# Bluetooth.net
KiCad netlist of a schematic drawn in Altium Designer
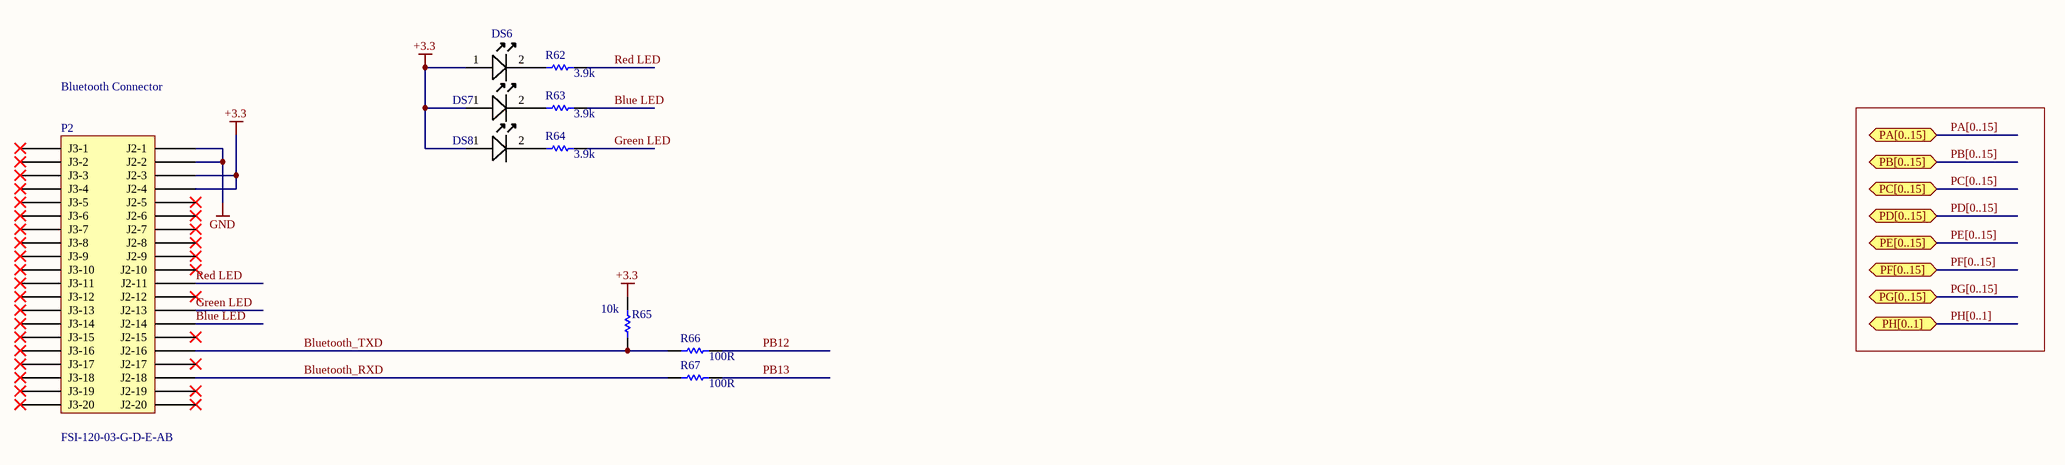
[diagram p0: Bluetooth.SchDoc]

(export (version "E")
  (design (tool "Eeschema 10.0.6"))
  (components
    (comp (ref "DS6")
      (value "Lite-On LTST-S220KGKT Green LED, 571 nm 2012 (0805) Side View, Rectangle Lens SMD package")
      (footprint "0805C_L")
      (fields
        (field (name "MANUFACTURER") "Vishay / Lite-On")
        (field (name "MANUFACTURER PART NUMBER") "LTST-S220KGKT")
      )
      (libsource (lib "*") (part "LED A/K"))
    )
    (comp (ref "DS7")
      (value "Lite-On LTST-S220KGKT Green LED, 571 nm 2012 (0805) Side View, Rectangle Lens SMD package")
      (footprint "0805C_L")
      (fields
        (field (name "MANUFACTURER") "Vishay / Lite-On")
        (field (name "MANUFACTURER PART NUMBER") "LTST-S220KGKT")
      )
      (libsource (lib "*") (part "LED A/K"))
    )
    (comp (ref "DS8")
      (value "Lite-On LTST-S220KGKT Green LED, 571 nm 2012 (0805) Side View, Rectangle Lens SMD package")
      (footprint "0805C_L")
      (fields
        (field (name "MANUFACTURER") "Vishay / Lite-On")
        (field (name "MANUFACTURER PART NUMBER") "LTST-S220KGKT")
      )
      (libsource (lib "*") (part "LED A/K"))
    )
    (comp (ref "P2")
      (value "FSI-120-03-G-D-E-AB")
      (footprint "FSI-120-03-G-D-E-AB")
      (fields
        (field (name "MANUFACTURER") "Samtec")
        (field (name "MANUFACTURER PART NUMBER") "FSI-120-03-G-D-E-AB")
      )
      (libsource (lib "ZLS_Schematic_lib") (part "FSI-120-03-G-D-E-AB"))
    )
    (comp (ref "R62")
      (value "CRCW08053K90FKEA")
      (footprint "RESC0805(2012)_M")
      (description "3.9 kOhms ±1% 0.125W, 1/8W Chip Resistor 0805 (2012 Metric) Automotive AEC-Q200 Thick Film")
      (fields
        (field (name "POWER") "0.125 W")
        (field (name "TOLERANCE") "1 %")
        (field (name "RESISTANCE") "3.9k")
      )
      (libsource (lib "Altium Content Vault") (part "RES"))
    )
    (comp (ref "R63")
      (value "CRCW08053K90FKEA")
      (footprint "RESC0805(2012)_M")
      (description "3.9 kOhms ±1% 0.125W, 1/8W Chip Resistor 0805 (2012 Metric) Automotive AEC-Q200 Thick Film")
      (fields
        (field (name "POWER") "0.125 W")
        (field (name "TOLERANCE") "1 %")
        (field (name "RESISTANCE") "3.9k")
      )
      (libsource (lib "Altium Content Vault") (part "RES"))
    )
    (comp (ref "R64")
      (value "CRCW08053K90FKEA")
      (footprint "RESC0805(2012)_M")
      (description "3.9 kOhms ±1% 0.125W, 1/8W Chip Resistor 0805 (2012 Metric) Automotive AEC-Q200 Thick Film")
      (fields
        (field (name "POWER") "0.125 W")
        (field (name "TOLERANCE") "1 %")
        (field (name "RESISTANCE") "3.9k")
      )
      (libsource (lib "Altium Content Vault") (part "RES"))
    )
    (comp (ref "R65")
      (value "CRCW080510K0FKEA")
      (footprint "RESC2013X50X30NL20T20")
      (description "10 kOhms ±1% 0.125W, 1/8W Chip Resistor 0805 (2012 Metric) Automotive AEC-Q200 Thick Film")
      (fields
        (field (name "MANUFACTURER") "Vishay Dale")
        (field (name "RESISTANCE") "10k")
        (field (name "TOLERANCE") "1%")
      )
      (libsource (lib "Altium Content Vault") (part "RES"))
    )
    (comp (ref "R66")
      (value "CRCW0805100RFKEA")
      (footprint "RESC2013X50X30LL20T20")
      (description "100 Ohms ±1% 0.125W, 1/8W Chip Resistor 0805 (2012 Metric) Thick Film")
      (fields
        (field (name "MANUFACTURER") "Vishay Dale")
        (field (name "RESISTANCE") "100R")
        (field (name "TOLERANCE") "1%")
      )
      (libsource (lib "Altium Content Vault") (part "RES"))
    )
    (comp (ref "R67")
      (value "CRCW0805100RFKEA")
      (footprint "RESC2013X50X30LL20T20")
      (description "100 Ohms ±1% 0.125W, 1/8W Chip Resistor 0805 (2012 Metric) Thick Film")
      (fields
        (field (name "MANUFACTURER") "Vishay Dale")
        (field (name "RESISTANCE") "100R")
        (field (name "TOLERANCE") "1%")
      )
      (libsource (lib "Altium Content Vault") (part "RES"))
    )
  )
  (nets
    (net (code "113") (name "+3.3") (class "Default")
      (node (ref "DS6") (pin "1") (pinfunction "A_1") (pintype "passive"))
      (node (ref "DS7") (pin "1") (pinfunction "A_1") (pintype "passive"))
      (node (ref "DS8") (pin "1") (pinfunction "A_1") (pintype "passive"))
      (node (ref "P2") (pin "J2-3") (pinfunction "J2-3_J2-3") (pintype "passive"))
      (node (ref "P2") (pin "J2-4") (pinfunction "J2-4_J2-4") (pintype "passive"))
      (node (ref "R65") (pin "2") (pinfunction "2_2") (pintype "passive"))
    )
    (net (code "114") (name "/Blue LED") (class "Default")
      (node (ref "P2") (pin "J2-14") (pinfunction "J2-14_J2-14") (pintype "passive"))
      (node (ref "R63") (pin "2") (pinfunction "2_2") (pintype "passive"))
    )
    (net (code "115") (name "/Bluetooth_RXD") (class "Default")
      (node (ref "P2") (pin "J2-18") (pinfunction "J2-18_J2-18") (pintype "passive"))
      (node (ref "R67") (pin "1") (pinfunction "1_1") (pintype "passive"))
    )
    (net (code "116") (name "/Bluetooth_TXD") (class "Default")
      (node (ref "P2") (pin "J2-16") (pinfunction "J2-16_J2-16") (pintype "passive"))
      (node (ref "R65") (pin "1") (pinfunction "1_1") (pintype "passive"))
      (node (ref "R66") (pin "1") (pinfunction "1_1") (pintype "passive"))
    )
    (net (code "117") (name "/Green LED") (class "Default")
      (node (ref "P2") (pin "J2-13") (pinfunction "J2-13_J2-13") (pintype "passive"))
      (node (ref "R64") (pin "2") (pinfunction "2_2") (pintype "passive"))
    )
    (net (code "119") (name "/PB12") (class "Default")
      (node (ref "R66") (pin "2") (pinfunction "2_2") (pintype "passive"))
    )
    (net (code "120") (name "/PB13") (class "Default")
      (node (ref "R67") (pin "2") (pinfunction "2_2") (pintype "passive"))
    )
    (net (code "128") (name "/Red LED") (class "Default")
      (node (ref "P2") (pin "J2-11") (pinfunction "J2-11_J2-11") (pintype "passive"))
      (node (ref "R62") (pin "2") (pinfunction "2_2") (pintype "passive"))
    )
    (net (code "129") (name "GND") (class "Default")
      (node (ref "P2") (pin "J2-1") (pinfunction "J2-1_J2-1") (pintype "passive"))
      (node (ref "P2") (pin "J2-2") (pinfunction "J2-2_J2-2") (pintype "passive"))
    )
    (net (code "130") (name "Net-(DS6-K)") (class "Default")
      (node (ref "DS6") (pin "2") (pinfunction "K_2") (pintype "passive"))
      (node (ref "R62") (pin "1") (pinfunction "1_1") (pintype "passive"))
    )
    (net (code "131") (name "Net-(DS7-K)") (class "Default")
      (node (ref "DS7") (pin "2") (pinfunction "K_2") (pintype "passive"))
      (node (ref "R63") (pin "1") (pinfunction "1_1") (pintype "passive"))
    )
    (net (code "132") (name "Net-(DS8-K)") (class "Default")
      (node (ref "DS8") (pin "2") (pinfunction "K_2") (pintype "passive"))
      (node (ref "R64") (pin "1") (pinfunction "1_1") (pintype "passive"))
    )
    (net (code "133") (name "unconnected-(P2-PadJ2-5)") (class "Default")
      (node (ref "P2") (pin "J2-5") (pinfunction "J2-5_J2-5") (pintype "passive+no_connect"))
    )
    (net (code "134") (name "unconnected-(P2-PadJ2-6)") (class "Default")
      (node (ref "P2") (pin "J2-6") (pinfunction "J2-6_J2-6") (pintype "passive+no_connect"))
    )
    (net (code "135") (name "unconnected-(P2-PadJ2-7)") (class "Default")
      (node (ref "P2") (pin "J2-7") (pinfunction "J2-7_J2-7") (pintype "passive+no_connect"))
    )
    (net (code "136") (name "unconnected-(P2-PadJ2-8)") (class "Default")
      (node (ref "P2") (pin "J2-8") (pinfunction "J2-8_J2-8") (pintype "passive+no_connect"))
    )
    (net (code "137") (name "unconnected-(P2-PadJ2-9)") (class "Default")
      (node (ref "P2") (pin "J2-9") (pinfunction "J2-9_J2-9") (pintype "passive+no_connect"))
    )
    (net (code "138") (name "unconnected-(P2-PadJ2-10)") (class "Default")
      (node (ref "P2") (pin "J2-10") (pinfunction "J2-10_J2-10") (pintype "passive+no_connect"))
    )
    (net (code "139") (name "unconnected-(P2-PadJ2-12)") (class "Default")
      (node (ref "P2") (pin "J2-12") (pinfunction "J2-12_J2-12") (pintype "passive+no_connect"))
    )
    (net (code "140") (name "unconnected-(P2-PadJ2-15)") (class "Default")
      (node (ref "P2") (pin "J2-15") (pinfunction "J2-15_J2-15") (pintype "passive+no_connect"))
    )
    (net (code "141") (name "unconnected-(P2-PadJ2-17)") (class "Default")
      (node (ref "P2") (pin "J2-17") (pinfunction "J2-17_J2-17") (pintype "passive+no_connect"))
    )
    (net (code "142") (name "unconnected-(P2-PadJ2-19)") (class "Default")
      (node (ref "P2") (pin "J2-19") (pinfunction "J2-19_J2-19") (pintype "passive+no_connect"))
    )
    (net (code "143") (name "unconnected-(P2-PadJ2-20)") (class "Default")
      (node (ref "P2") (pin "J2-20") (pinfunction "J2-20_J2-20") (pintype "passive+no_connect"))
    )
    (net (code "144") (name "unconnected-(P2-PadJ3-1)") (class "Default")
      (node (ref "P2") (pin "J3-1") (pinfunction "J3-1_J3-1") (pintype "passive+no_connect"))
    )
    (net (code "145") (name "unconnected-(P2-PadJ3-2)") (class "Default")
      (node (ref "P2") (pin "J3-2") (pinfunction "J3-2_J3-2") (pintype "passive+no_connect"))
    )
    (net (code "146") (name "unconnected-(P2-PadJ3-3)") (class "Default")
      (node (ref "P2") (pin "J3-3") (pinfunction "J3-3_J3-3") (pintype "passive+no_connect"))
    )
    (net (code "147") (name "unconnected-(P2-PadJ3-4)") (class "Default")
      (node (ref "P2") (pin "J3-4") (pinfunction "J3-4_J3-4") (pintype "passive+no_connect"))
    )
    (net (code "148") (name "unconnected-(P2-PadJ3-5)") (class "Default")
      (node (ref "P2") (pin "J3-5") (pinfunction "J3-5_J3-5") (pintype "passive+no_connect"))
    )
    (net (code "149") (name "unconnected-(P2-PadJ3-6)") (class "Default")
      (node (ref "P2") (pin "J3-6") (pinfunction "J3-6_J3-6") (pintype "passive+no_connect"))
    )
    (net (code "150") (name "unconnected-(P2-PadJ3-7)") (class "Default")
      (node (ref "P2") (pin "J3-7") (pinfunction "J3-7_J3-7") (pintype "passive+no_connect"))
    )
    (net (code "151") (name "unconnected-(P2-PadJ3-8)") (class "Default")
      (node (ref "P2") (pin "J3-8") (pinfunction "J3-8_J3-8") (pintype "passive+no_connect"))
    )
    (net (code "152") (name "unconnected-(P2-PadJ3-9)") (class "Default")
      (node (ref "P2") (pin "J3-9") (pinfunction "J3-9_J3-9") (pintype "passive+no_connect"))
    )
    (net (code "153") (name "unconnected-(P2-PadJ3-10)") (class "Default")
      (node (ref "P2") (pin "J3-10") (pinfunction "J3-10_J3-10") (pintype "passive+no_connect"))
    )
    (net (code "154") (name "unconnected-(P2-PadJ3-11)") (class "Default")
      (node (ref "P2") (pin "J3-11") (pinfunction "J3-11_J3-11") (pintype "passive+no_connect"))
    )
    (net (code "155") (name "unconnected-(P2-PadJ3-12)") (class "Default")
      (node (ref "P2") (pin "J3-12") (pinfunction "J3-12_J3-12") (pintype "passive+no_connect"))
    )
    (net (code "156") (name "unconnected-(P2-PadJ3-13)") (class "Default")
      (node (ref "P2") (pin "J3-13") (pinfunction "J3-13_J3-13") (pintype "passive+no_connect"))
    )
    (net (code "157") (name "unconnected-(P2-PadJ3-14)") (class "Default")
      (node (ref "P2") (pin "J3-14") (pinfunction "J3-14_J3-14") (pintype "passive+no_connect"))
    )
    (net (code "158") (name "unconnected-(P2-PadJ3-15)") (class "Default")
      (node (ref "P2") (pin "J3-15") (pinfunction "J3-15_J3-15") (pintype "passive+no_connect"))
    )
    (net (code "159") (name "unconnected-(P2-PadJ3-16)") (class "Default")
      (node (ref "P2") (pin "J3-16") (pinfunction "J3-16_J3-16") (pintype "passive+no_connect"))
    )
    (net (code "160") (name "unconnected-(P2-PadJ3-17)") (class "Default")
      (node (ref "P2") (pin "J3-17") (pinfunction "J3-17_J3-17") (pintype "passive+no_connect"))
    )
    (net (code "161") (name "unconnected-(P2-PadJ3-18)") (class "Default")
      (node (ref "P2") (pin "J3-18") (pinfunction "J3-18_J3-18") (pintype "passive+no_connect"))
    )
    (net (code "162") (name "unconnected-(P2-PadJ3-19)") (class "Default")
      (node (ref "P2") (pin "J3-19") (pinfunction "J3-19_J3-19") (pintype "passive+no_connect"))
    )
    (net (code "163") (name "unconnected-(P2-PadJ3-20)") (class "Default")
      (node (ref "P2") (pin "J3-20") (pinfunction "J3-20_J3-20") (pintype "passive+no_connect"))
    )
  )
)
